# ProPrj_13cmPA-V1_V1_2025-12-29.net
KiCad netlist of a schematic drawn in EasyEDA Pro
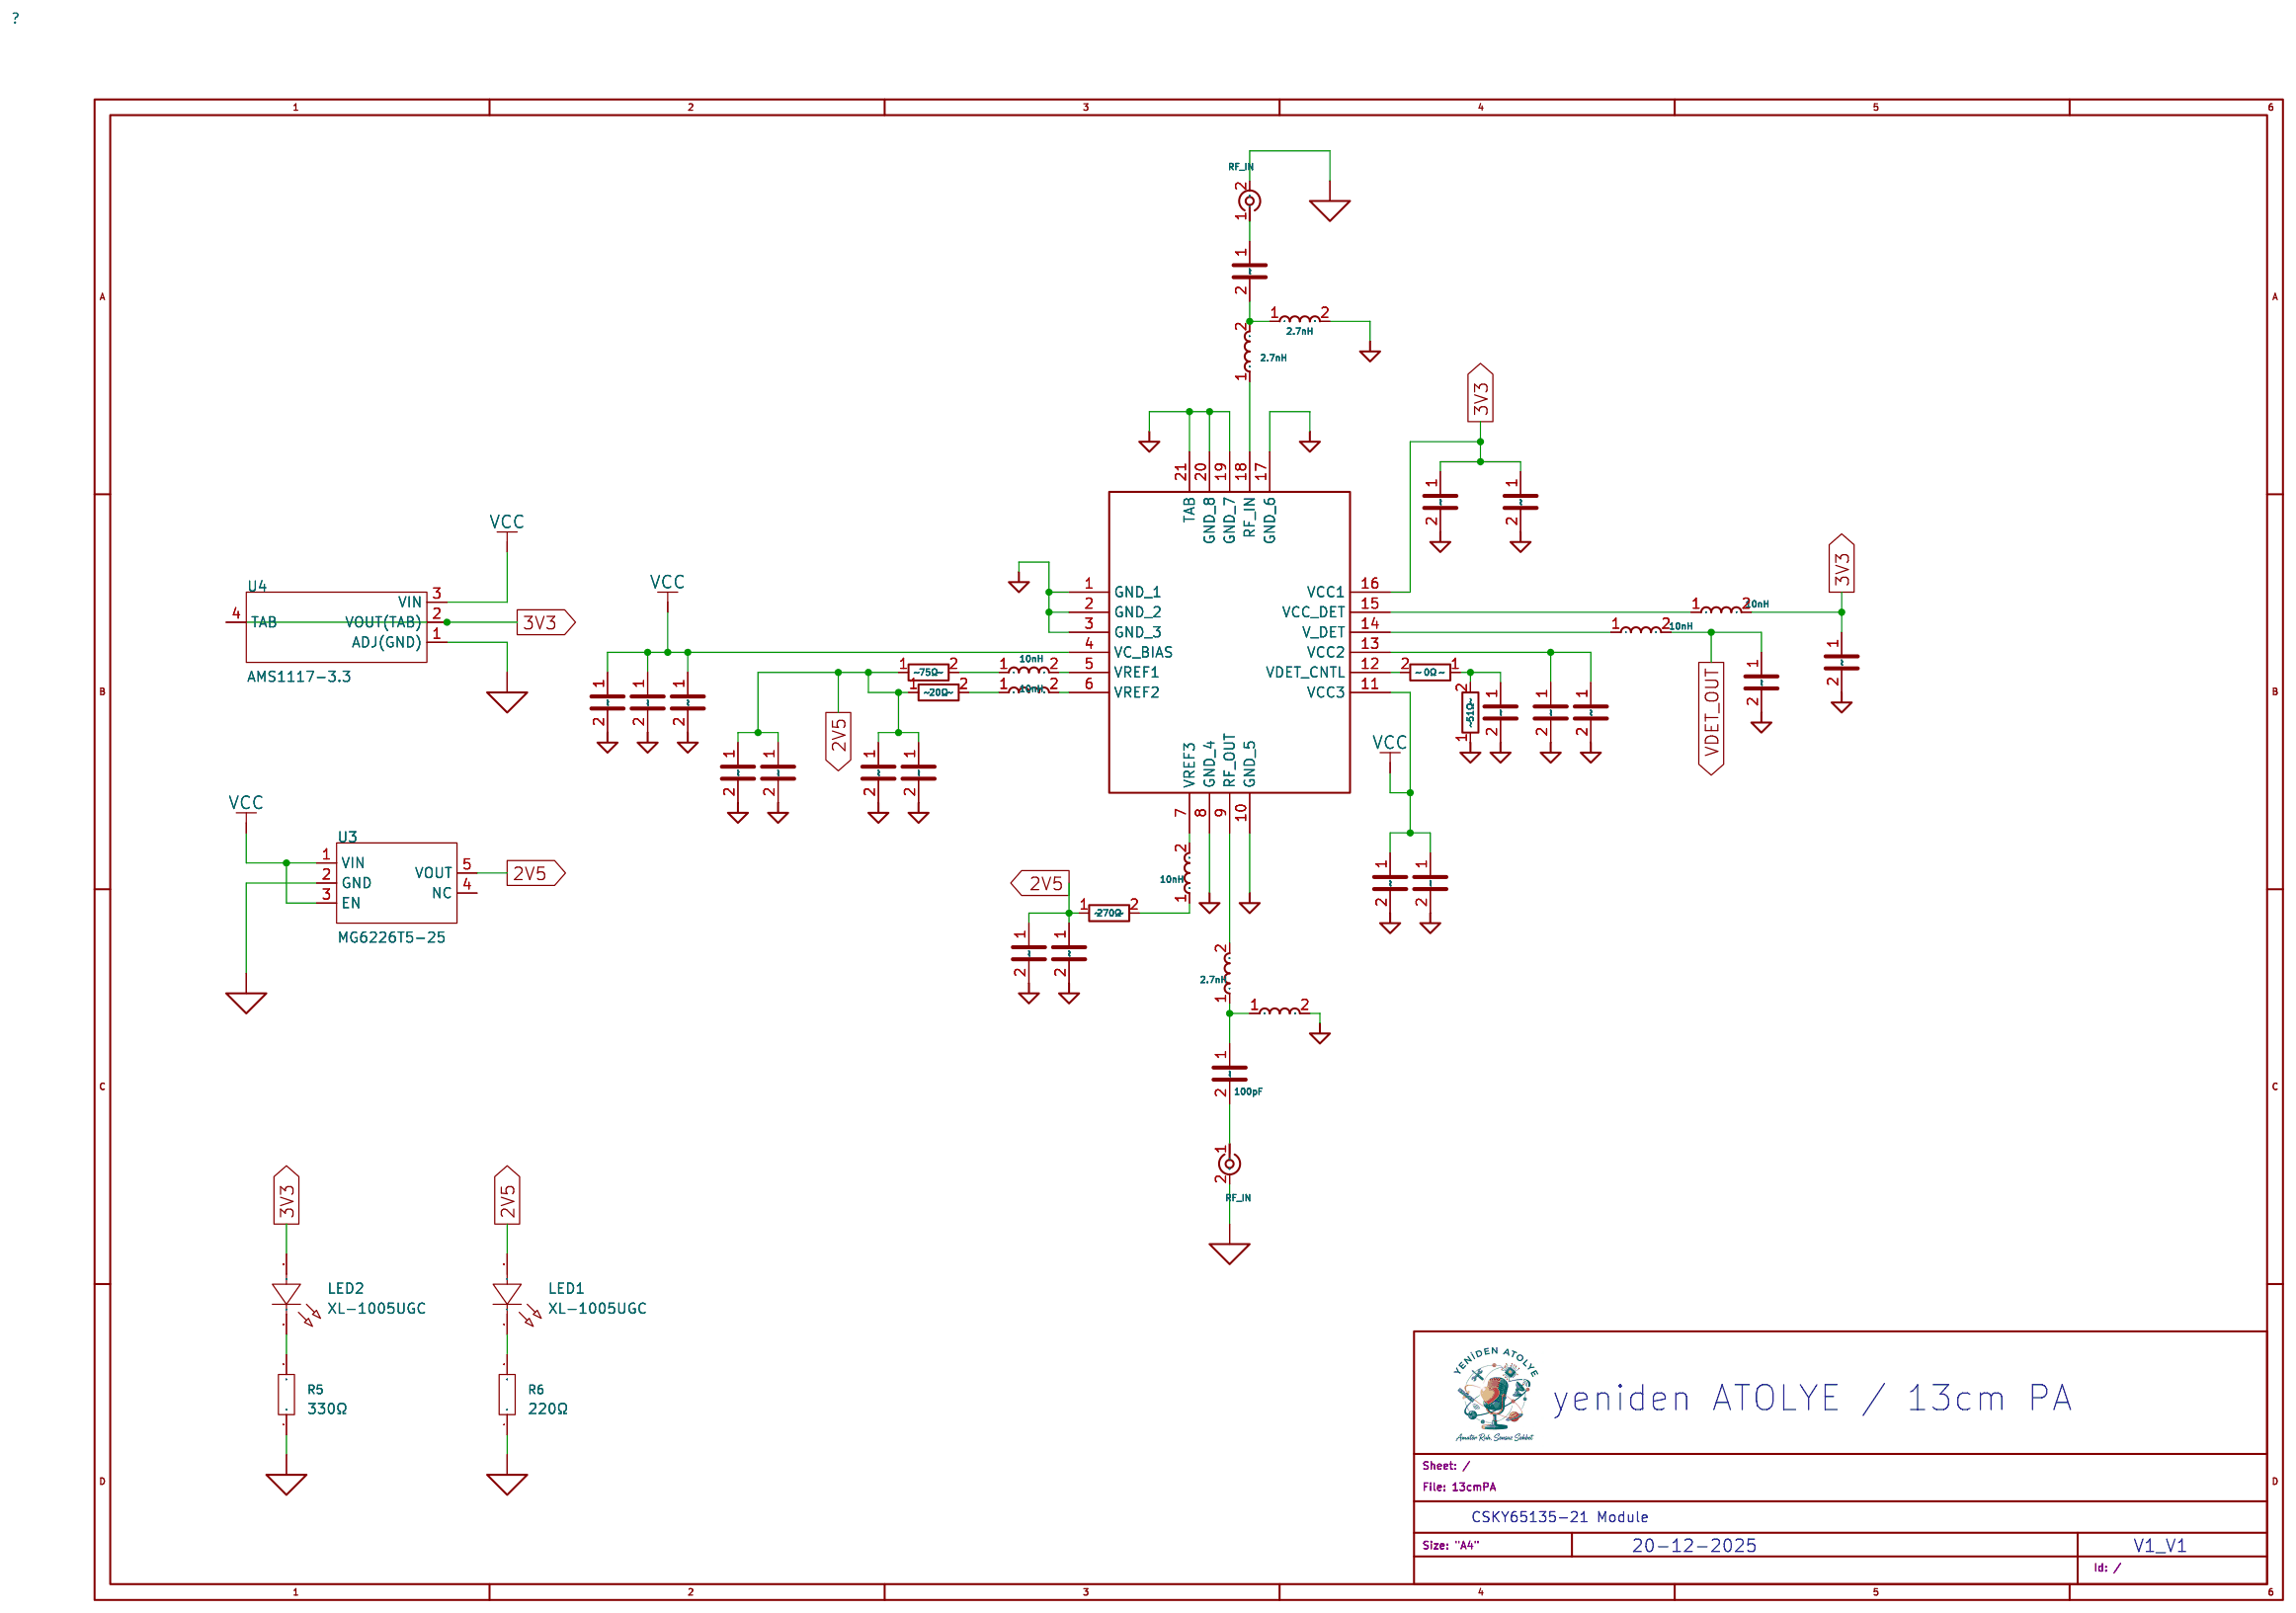
[diagram p0: schematic sheet]

(export (version "E")
  (design (tool "Eeschema 10.0.6"))
  (components
    (comp (ref "C1")
      (value "8.2pF")
      (footprint "easyedapro:Capacitor_SMD:C_0402_1005Metric")
      (description "Capacitance:8.2pF Voltage Rating:50V Temperature Coefficient:C0G")
      (fields (field (name "Manufacturer Part") "0402CG8R2C500NT") (field (name "Manufacturer") "FH(风华)"))
      (libsource (lib "easyedapro") (part "Device_C"))
    )
    (comp (ref "C2")
      (value "10uF")
      (footprint "easyedapro:Capacitor_SMD:C_0402_1005Metric")
      (description "Capacitance:10uF Tolerance:±10% Tolerance:±10% Voltage Rating:10V Temperature Coefficient:X7R")
      (fields (field (name "Manufacturer Part") "C0805X106K010T") (field (name "Manufacturer") "IHHEC(禾伸堂)"))
      (libsource (lib "easyedapro") (part "Device_C"))
    )
    (comp (ref "C3")
      (value "100nF")
      (footprint "easyedapro:Capacitor_SMD:C_0402_1005Metric")
      (description "Capacitance:100nF Tolerance:±10% Tolerance:±10% Voltage Rating:50V Temperature Coefficient:X7R")
      (fields (field (name "Manufacturer Part") "C0402X104K050T") (field (name "Manufacturer") "IHHEC(禾伸堂)"))
      (libsource (lib "easyedapro") (part "Device_C"))
    )
    (comp (ref "C4")
      (value "8.2pF")
      (footprint "easyedapro:Capacitor_SMD:C_0402_1005Metric")
      (description "Capacitance:8.2pF Voltage Rating:50V Temperature Coefficient:C0G")
      (fields (field (name "Manufacturer Part") "0402CG8R2C500NT") (field (name "Manufacturer") "FH(风华)"))
      (libsource (lib "easyedapro") (part "Device_C"))
    )
    (comp (ref "C5")
      (value "100nF")
      (footprint "easyedapro:Capacitor_SMD:C_0402_1005Metric")
      (description "Capacitance:100nF Tolerance:±10% Tolerance:±10% Voltage Rating:50V Temperature Coefficient:X7R")
      (fields (field (name "Manufacturer Part") "C0402X104K050T") (field (name "Manufacturer") "IHHEC(禾伸堂)"))
      (libsource (lib "easyedapro") (part "Device_C"))
    )
    (comp (ref "C6")
      (value "8.2pF")
      (footprint "easyedapro:Capacitor_SMD:C_0402_1005Metric")
      (description "Capacitance:8.2pF Voltage Rating:50V Temperature Coefficient:C0G")
      (fields (field (name "Manufacturer Part") "0402CG8R2C500NT") (field (name "Manufacturer") "FH(风华)"))
      (libsource (lib "easyedapro") (part "Device_C"))
    )
    (comp (ref "C7")
      (value "10uF")
      (footprint "easyedapro:Capacitor_SMD:C_0402_1005Metric")
      (description "Capacitance:10uF Tolerance:±10% Tolerance:±10% Voltage Rating:10V Temperature Coefficient:X7R")
      (fields (field (name "Manufacturer Part") "C0805X106K010T") (field (name "Manufacturer") "IHHEC(禾伸堂)"))
      (libsource (lib "easyedapro") (part "Device_C"))
    )
    (comp (ref "C8")
      (value "100nF")
      (footprint "easyedapro:Capacitor_SMD:C_0402_1005Metric")
      (description "Capacitance:100nF Tolerance:±10% Tolerance:±10% Voltage Rating:50V Temperature Coefficient:X7R")
      (fields (field (name "Manufacturer Part") "C0402X104K050T") (field (name "Manufacturer") "IHHEC(禾伸堂)"))
      (libsource (lib "easyedapro") (part "Device_C"))
    )
    (comp (ref "C9")
      (value "100nF")
      (footprint "easyedapro:Capacitor_SMD:C_0402_1005Metric")
      (description "Capacitance:100nF Tolerance:±10% Tolerance:±10% Voltage Rating:50V Temperature Coefficient:X7R")
      (fields (field (name "Manufacturer Part") "C0402X104K050T") (field (name "Manufacturer") "IHHEC(禾伸堂)"))
      (libsource (lib "easyedapro") (part "Device_C"))
    )
    (comp (ref "C10")
      (value "8.2pF")
      (footprint "easyedapro:Capacitor_SMD:C_0402_1005Metric")
      (description "Capacitance:8.2pF Voltage Rating:50V Temperature Coefficient:C0G")
      (fields (field (name "Manufacturer Part") "0402CG8R2C500NT") (field (name "Manufacturer") "FH(风华)"))
      (libsource (lib "easyedapro") (part "Device_C"))
    )
    (comp (ref "C11")
      (value "3.3nF")
      (footprint "easyedapro:Capacitor_SMD:C_0402_1005Metric")
      (description "Capacitance:3.3nF Tolerance:±10% Tolerance:±10% Voltage Rating:50V Temperature Coefficient:X7R")
      (fields
        (field (name "Manufacturer Part") "CC0402KRX7R9BB332")
        (field (name "Manufacturer") "YAGEO(国巨)")
      )
      (libsource (lib "easyedapro") (part "Device_C"))
    )
    (comp (ref "C12")
      (value "8.2pF")
      (footprint "easyedapro:Capacitor_SMD:C_0402_1005Metric")
      (description "Capacitance:8.2pF Voltage Rating:50V Temperature Coefficient:C0G")
      (fields (field (name "Manufacturer Part") "0402CG8R2C500NT") (field (name "Manufacturer") "FH(风华)"))
      (libsource (lib "easyedapro") (part "Device_C"))
    )
    (comp (ref "C13")
      (value "8.2pF")
      (footprint "easyedapro:Capacitor_SMD:C_0402_1005Metric")
      (description "Capacitance:8.2pF Voltage Rating:50V Temperature Coefficient:C0G")
      (fields (field (name "Manufacturer Part") "0402CG8R2C500NT") (field (name "Manufacturer") "FH(风华)"))
      (libsource (lib "easyedapro") (part "Device_C"))
    )
    (comp (ref "C14")
      (value "100nF")
      (footprint "easyedapro:Capacitor_SMD:C_0402_1005Metric")
      (description "Capacitance:100nF Tolerance:±10% Tolerance:±10% Voltage Rating:50V Temperature Coefficient:X7R")
      (fields (field (name "Manufacturer Part") "C0402X104K050T") (field (name "Manufacturer") "IHHEC(禾伸堂)"))
      (libsource (lib "easyedapro") (part "Device_C"))
    )
    (comp (ref "C15")
      (value "270pF")
      (footprint "easyedapro:Capacitor_SMD:C_0402_1005Metric")
      (description "Capacitance:270pF Tolerance:±10% Tolerance:±10% Voltage Rating:50V Temperature Coefficient:X7R")
      (fields
        (field (name "Manufacturer Part") "CC0402KRX7R9BB271")
        (field (name "Manufacturer") "YAGEO(国巨)")
      )
      (libsource (lib "easyedapro") (part "Device_C"))
    )
    (comp (ref "C16")
      (value "C0402A101J500NT")
      (footprint "easyedapro:Capacitor_SMD:C_0402_1005Metric")
      (fields (field (name "Manufacturer") "TORCH(火炬)"))
      (libsource (lib "easyedapro") (part "Device_C"))
    )
    (comp (ref "C17")
      (value "10uF")
      (footprint "easyedapro:Capacitor_SMD:C_0402_1005Metric")
      (description "Capacitance:10uF Tolerance:±10% Tolerance:±10% Voltage Rating:10V Temperature Coefficient:X7R")
      (fields (field (name "Manufacturer Part") "C0805X106K010T") (field (name "Manufacturer") "IHHEC(禾伸堂)"))
      (libsource (lib "easyedapro") (part "Device_C"))
    )
    (comp (ref "C18")
      (value "100pF")
      (footprint "easyedapro:Capacitor_SMD:C_0402_1005Metric")
      (description "Capacitance:100pF Tolerance:±5% Tolerance:±5% Voltage Rating:50V Temperature Coefficient:C0G")
      (fields
        (field (name "Manufacturer Part") "CL21C101JBANNNC")
        (field (name "Manufacturer") "SAMSUNG(三星)")
      )
      (libsource (lib "easyedapro") (part "Device_C"))
    )
    (comp (ref "C19")
      (value "100pF")
      (footprint "easyedapro:Capacitor_SMD:C_0402_1005Metric")
      (description "Capacitance:100pF Tolerance:±5% Tolerance:±5% Voltage Rating:50V Temperature Coefficient:C0G")
      (fields
        (field (name "Manufacturer Part") "CL21C101JBANNNC")
        (field (name "Manufacturer") "SAMSUNG(三星)")
      )
      (libsource (lib "easyedapro") (part "Device_C"))
    )
    (comp (ref "C20")
      (value "100nF")
      (footprint "easyedapro:Capacitor_SMD:C_0402_1005Metric")
      (description "Capacitance:100nF Tolerance:±10% Tolerance:±10% Voltage Rating:50V Temperature Coefficient:X7R")
      (fields (field (name "Manufacturer Part") "C0402X104K050T") (field (name "Manufacturer") "IHHEC(禾伸堂)"))
      (libsource (lib "easyedapro") (part "Device_C"))
    )
    (comp (ref "IC1")
      (value "SKY65135-21")
      (footprint "easyedapro:QFN100P600X600X155-21N")
      (libsource (lib "easyedapro") (part "SKY65135-21_SKY65135-21"))
    )
    (comp (ref "J1")
      (value "RF_IN")
      (footprint "easyedapro:Connector_Coaxial:SMA_Amphenol_132289_EdgeMount")
      (description "small coaxial connector (BNC, SMA, SMB, SMC, Cinch/RCA, LEMO, ...)")
      (libsource (lib "easyedapro") (part "Connector_Conn_Coaxial_Small"))
    )
    (comp (ref "J2")
      (value "RF_IN")
      (footprint "easyedapro:Connector_Coaxial:SMA_Amphenol_132289_EdgeMount")
      (description "small coaxial connector (BNC, SMA, SMB, SMC, Cinch/RCA, LEMO, ...)")
      (libsource (lib "easyedapro") (part "Connector_Conn_Coaxial_Small"))
    )
    (comp (ref "L1")
      (value "10nH")
      (footprint "easyedapro:Inductor_SMD:L_0402_1005Metric")
      (fields (field (name "Manufacturer Part") "LQG15HS10NJ02D") (field (name "Manufacturer") "muRata(村田)"))
      (libsource (lib "easyedapro") (part "Device_L"))
    )
    (comp (ref "L2")
      (value "10nH")
      (footprint "easyedapro:Inductor_SMD:L_0402_1005Metric")
      (fields (field (name "Manufacturer Part") "LQG15HS10NJ02D") (field (name "Manufacturer") "muRata(村田)"))
      (libsource (lib "easyedapro") (part "Device_L"))
    )
    (comp (ref "L3")
      (value "2.7nH")
      (footprint "easyedapro:Inductor_SMD:L_0402_1005Metric")
      (fields (field (name "Manufacturer Part") "MLG1005S2N7BT000") (field (name "Manufacturer") "TDK"))
      (libsource (lib "easyedapro") (part "Device_L"))
    )
    (comp (ref "L4")
      (value "2.7nH")
      (footprint "easyedapro:Inductor_SMD:L_0402_1005Metric")
      (fields (field (name "Manufacturer Part") "MLG1005S2N7BT000") (field (name "Manufacturer") "TDK"))
      (libsource (lib "easyedapro") (part "Device_L"))
    )
    (comp (ref "L5")
      (value "2.7nH")
      (footprint "easyedapro:Inductor_SMD:L_0402_1005Metric")
      (fields (field (name "Manufacturer Part") "MLG1005S2N7BT000") (field (name "Manufacturer") "TDK"))
      (libsource (lib "easyedapro") (part "Device_L"))
    )
    (comp (ref "L6")
      (value "2.7nH")
      (footprint "easyedapro:Inductor_SMD:L_0402_1005Metric")
      (fields (field (name "Manufacturer Part") "MLG1005S2N7BT000") (field (name "Manufacturer") "TDK"))
      (libsource (lib "easyedapro") (part "Device_L"))
    )
    (comp (ref "L7")
      (value "10nH")
      (footprint "easyedapro:Inductor_SMD:L_0402_1005Metric")
      (fields (field (name "Manufacturer Part") "LQG15HS10NJ02D") (field (name "Manufacturer") "muRata(村田)"))
      (libsource (lib "easyedapro") (part "Device_L"))
    )
    (comp (ref "L8")
      (value "10nH")
      (footprint "easyedapro:Inductor_SMD:L_0402_1005Metric")
      (fields (field (name "Manufacturer Part") "LQG15HS10NJ02D") (field (name "Manufacturer") "muRata(村田)"))
      (libsource (lib "easyedapro") (part "Device_L"))
    )
    (comp (ref "L9")
      (value "10nH")
      (footprint "easyedapro:Inductor_SMD:L_0402_1005Metric")
      (fields (field (name "Manufacturer Part") "LQG15HS10NJ02D") (field (name "Manufacturer") "muRata(村田)"))
      (libsource (lib "easyedapro") (part "Device_L"))
    )
    (comp (ref "LED1")
      (value "XL-1005UGC")
      (footprint "easyedapro:LED0402-RD_GREEN")
      (fields (field (name "Manufacturer") "XINGLIGHT(成兴光)"))
      (libsource (lib "easyedapro") (part "XL-1005UGC"))
    )
    (comp (ref "LED2")
      (value "XL-1005UGC")
      (footprint "easyedapro:LED0402-RD_GREEN")
      (fields (field (name "Manufacturer") "XINGLIGHT(成兴光)"))
      (libsource (lib "easyedapro") (part "XL-1005UGC"))
    )
    (comp (ref "R1")
      (value "75Ω")
      (footprint "easyedapro:Resistor_SMD:R_0402_1005Metric")
      (fields (field (name "Manufacturer Part") "CR0402FF75R0G") (field (name "Manufacturer") "LIZ(丽智电子)"))
      (libsource (lib "easyedapro") (part "Device_R"))
    )
    (comp (ref "R2")
      (value "20Ω")
      (footprint "easyedapro:Resistor_SMD:R_0402_1005Metric")
      (fields (field (name "Manufacturer Part") "CR0402FF20R0G") (field (name "Manufacturer") "LIZ(丽智电子)"))
      (libsource (lib "easyedapro") (part "Device_R"))
    )
    (comp (ref "R3")
      (value "0Ω")
      (footprint "easyedapro:Resistor_SMD:R_0402_1005Metric")
      (fields (field (name "Manufacturer Part") "SCR0402J0R") (field (name "Manufacturer") "VO(翔胜)"))
      (libsource (lib "easyedapro") (part "Device_R"))
    )
    (comp (ref "R4")
      (value "51Ω")
      (footprint "easyedapro:Resistor_SMD:R_0402_1005Metric")
      (fields (field (name "Manufacturer Part") "RC0402FR-0751RL") (field (name "Manufacturer") "YAGEO(国巨)"))
      (libsource (lib "easyedapro") (part "Device_R"))
    )
    (comp (ref "R5")
      (value "330Ω")
      (footprint "easyedapro:R0402")
      (fields
        (field (name "Manufacturer Part") "0402WGF3300TCE")
        (field (name "Manufacturer") "UNI-ROYAL(厚声)")
      )
      (libsource (lib "easyedapro") (part "0402WGF3300TCE"))
    )
    (comp (ref "R6")
      (value "220Ω")
      (footprint "easyedapro:R0402")
      (fields
        (field (name "Manufacturer Part") "0402WGF2200TCE")
        (field (name "Manufacturer") "UNI-ROYAL(厚声)")
      )
      (libsource (lib "easyedapro") (part "0402WGF2200TCE"))
    )
    (comp (ref "R7")
      (value "270Ω")
      (footprint "easyedapro:Resistor_SMD:R_0402_1005Metric")
      (fields (field (name "Manufacturer Part") "CR0402JF0271G") (field (name "Manufacturer") "LIZ(丽智电子)"))
      (libsource (lib "easyedapro") (part "Device_R"))
    )
    (comp (ref "U3")
      (value "MG6226T5-25")
      (footprint "easyedapro:SOT-23-5_L2.9-W1.6-P0.95-LS2.8-BL")
      (fields (field (name "Manufacturer") "Megain(美佳音)"))
      (libsource (lib "easyedapro") (part "MG6226T5-25"))
    )
    (comp (ref "U4")
      (value "AMS1117-3.3")
      (footprint "easyedapro:SOT-223-4_L6.5-W3.5-P2.30-LS7.0-BR")
      (fields (field (name "Manufacturer") "UMW(友台半导体)"))
      (libsource (lib "easyedapro") (part "AMS1117-3.3_C347222"))
    )
  )
  (nets
    (net (code "1") (name "2V5") (class "Default")
      (node (ref "C10") (pin "1") (pinfunction "~_1") (pintype "unspecified"))
      (node (ref "C3") (pin "1") (pinfunction "~_1") (pintype "unspecified"))
      (node (ref "C4") (pin "1") (pinfunction "~_1") (pintype "unspecified"))
      (node (ref "C5") (pin "1") (pinfunction "~_1") (pintype "unspecified"))
      (node (ref "C6") (pin "1") (pinfunction "~_1") (pintype "unspecified"))
      (node (ref "C9") (pin "1") (pinfunction "~_1") (pintype "unspecified"))
      (node (ref "LED1") (pin "2") (pinfunction "A_2") (pintype "unspecified"))
      (node (ref "R1") (pin "1") (pinfunction "~_1") (pintype "unspecified"))
      (node (ref "R2") (pin "1") (pinfunction "~_1") (pintype "unspecified"))
      (node (ref "R7") (pin "1") (pinfunction "~_1") (pintype "unspecified"))
      (node (ref "U3") (pin "5") (pinfunction "VOUT_5") (pintype "unspecified"))
    )
    (net (code "2") (name "3V3") (class "Default")
      (node (ref "C11") (pin "1") (pinfunction "~_1") (pintype "unspecified"))
      (node (ref "C7") (pin "1") (pinfunction "~_1") (pintype "unspecified"))
      (node (ref "C8") (pin "1") (pinfunction "~_1") (pintype "unspecified"))
      (node (ref "IC1") (pin "16") (pinfunction "VCC1_16") (pintype "unspecified"))
      (node (ref "L1") (pin "2") (pinfunction "2_2") (pintype "unspecified"))
      (node (ref "LED2") (pin "2") (pinfunction "A_2") (pintype "unspecified"))
      (node (ref "U4") (pin "2") (pinfunction "VOUT(TAB)_2") (pintype "unspecified"))
      (node (ref "U4") (pin "4") (pinfunction "TAB_4") (pintype "unspecified"))
    )
    (net (code "3") (name "GND") (class "Default")
      (node (ref "C1") (pin "2") (pinfunction "~_2") (pintype "unspecified"))
      (node (ref "C10") (pin "2") (pinfunction "~_2") (pintype "unspecified"))
      (node (ref "C11") (pin "2") (pinfunction "~_2") (pintype "unspecified"))
      (node (ref "C12") (pin "2") (pinfunction "~_2") (pintype "unspecified"))
      (node (ref "C13") (pin "2") (pinfunction "~_2") (pintype "unspecified"))
      (node (ref "C14") (pin "2") (pinfunction "~_2") (pintype "unspecified"))
      (node (ref "C15") (pin "2") (pinfunction "~_2") (pintype "unspecified"))
      (node (ref "C16") (pin "2") (pinfunction "~_2") (pintype "unspecified"))
      (node (ref "C17") (pin "2") (pinfunction "~_2") (pintype "unspecified"))
      (node (ref "C2") (pin "2") (pinfunction "~_2") (pintype "unspecified"))
      (node (ref "C20") (pin "2") (pinfunction "~_2") (pintype "unspecified"))
      (node (ref "C3") (pin "2") (pinfunction "~_2") (pintype "unspecified"))
      (node (ref "C4") (pin "2") (pinfunction "~_2") (pintype "unspecified"))
      (node (ref "C5") (pin "2") (pinfunction "~_2") (pintype "unspecified"))
      (node (ref "C6") (pin "2") (pinfunction "~_2") (pintype "unspecified"))
      (node (ref "C7") (pin "2") (pinfunction "~_2") (pintype "unspecified"))
      (node (ref "C8") (pin "2") (pinfunction "~_2") (pintype "unspecified"))
      (node (ref "C9") (pin "2") (pinfunction "~_2") (pintype "unspecified"))
      (node (ref "IC1") (pin "1") (pinfunction "GND_1_1") (pintype "unspecified"))
      (node (ref "IC1") (pin "10") (pinfunction "GND_5_10") (pintype "unspecified"))
      (node (ref "IC1") (pin "17") (pinfunction "GND_6_17") (pintype "unspecified"))
      (node (ref "IC1") (pin "19") (pinfunction "GND_7_19") (pintype "unspecified"))
      (node (ref "IC1") (pin "2") (pinfunction "GND_2_2") (pintype "unspecified"))
      (node (ref "IC1") (pin "20") (pinfunction "GND_8_20") (pintype "unspecified"))
      (node (ref "IC1") (pin "21") (pinfunction "TAB_21") (pintype "unspecified"))
      (node (ref "IC1") (pin "3") (pinfunction "GND_3_3") (pintype "unspecified"))
      (node (ref "IC1") (pin "8") (pinfunction "GND_4_8") (pintype "unspecified"))
      (node (ref "J1") (pin "2") (pinfunction "Ext_2") (pintype "unspecified"))
      (node (ref "J2") (pin "2") (pinfunction "Ext_2") (pintype "unspecified"))
      (node (ref "L4") (pin "2") (pinfunction "2_2") (pintype "unspecified"))
      (node (ref "L6") (pin "2") (pinfunction "2_2") (pintype "unspecified"))
      (node (ref "R4") (pin "1") (pinfunction "~_1") (pintype "unspecified"))
      (node (ref "R5") (pin "1") (pinfunction "1_1") (pintype "input"))
      (node (ref "R6") (pin "1") (pinfunction "1_1") (pintype "input"))
      (node (ref "U3") (pin "2") (pinfunction "GND_2") (pintype "unspecified"))
      (node (ref "U4") (pin "1") (pinfunction "ADJ(GND)_1") (pintype "unspecified"))
    )
    (net (code "4") (name "Net-(C15-~-Pad1)") (class "Default")
      (node (ref "C15") (pin "1") (pinfunction "~_1") (pintype "unspecified"))
      (node (ref "R3") (pin "1") (pinfunction "~_1") (pintype "unspecified"))
      (node (ref "R4") (pin "2") (pinfunction "~_2") (pintype "unspecified"))
    )
    (net (code "5") (name "Net-(C18-~-Pad2)") (class "Default")
      (node (ref "C18") (pin "2") (pinfunction "~_2") (pintype "unspecified"))
      (node (ref "L3") (pin "2") (pinfunction "2_2") (pintype "unspecified"))
      (node (ref "L4") (pin "1") (pinfunction "1_1") (pintype "unspecified"))
    )
    (net (code "6") (name "Net-(C19-~-Pad1)") (class "Default")
      (node (ref "C19") (pin "1") (pinfunction "~_1") (pintype "unspecified"))
      (node (ref "L5") (pin "1") (pinfunction "1_1") (pintype "unspecified"))
      (node (ref "L6") (pin "1") (pinfunction "1_1") (pintype "unspecified"))
    )
    (net (code "7") (name "Net-(IC1-RF_IN)") (class "Default")
      (node (ref "IC1") (pin "18") (pinfunction "RF_IN_18") (pintype "input"))
      (node (ref "L3") (pin "1") (pinfunction "1_1") (pintype "unspecified"))
    )
    (net (code "8") (name "Net-(IC1-RF_OUT)") (class "Default")
      (node (ref "IC1") (pin "9") (pinfunction "RF_OUT_9") (pintype "output"))
      (node (ref "L5") (pin "2") (pinfunction "2_2") (pintype "unspecified"))
    )
    (net (code "9") (name "Net-(IC1-VCC2)") (class "Default")
      (node (ref "C13") (pin "1") (pinfunction "~_1") (pintype "unspecified"))
      (node (ref "C14") (pin "1") (pinfunction "~_1") (pintype "unspecified"))
      (node (ref "IC1") (pin "13") (pinfunction "VCC2_13") (pintype "unspecified"))
    )
    (net (code "10") (name "Net-(IC1-VCC_DET)") (class "Default")
      (node (ref "IC1") (pin "15") (pinfunction "VCC_DET_15") (pintype "unspecified"))
      (node (ref "L1") (pin "1") (pinfunction "1_1") (pintype "unspecified"))
    )
    (net (code "11") (name "Net-(IC1-VDET_CNTL)") (class "Default")
      (node (ref "IC1") (pin "12") (pinfunction "VDET_CNTL_12") (pintype "unspecified"))
      (node (ref "R3") (pin "2") (pinfunction "~_2") (pintype "unspecified"))
    )
    (net (code "12") (name "Net-(IC1-VREF1)") (class "Default")
      (node (ref "IC1") (pin "5") (pinfunction "VREF1_5") (pintype "input"))
      (node (ref "L8") (pin "2") (pinfunction "2_2") (pintype "unspecified"))
    )
    (net (code "13") (name "Net-(IC1-VREF2)") (class "Default")
      (node (ref "IC1") (pin "6") (pinfunction "VREF2_6") (pintype "input"))
      (node (ref "L9") (pin "2") (pinfunction "2_2") (pintype "unspecified"))
    )
    (net (code "14") (name "Net-(IC1-VREF3)") (class "Default")
      (node (ref "IC1") (pin "7") (pinfunction "VREF3_7") (pintype "input"))
      (node (ref "L7") (pin "2") (pinfunction "2_2") (pintype "unspecified"))
    )
    (net (code "15") (name "Net-(IC1-V_DET)") (class "Default")
      (node (ref "IC1") (pin "14") (pinfunction "V_DET_14") (pintype "unspecified"))
      (node (ref "L2") (pin "1") (pinfunction "1_1") (pintype "unspecified"))
    )
    (net (code "16") (name "Net-(J1-In)") (class "Default")
      (node (ref "C18") (pin "1") (pinfunction "~_1") (pintype "unspecified"))
      (node (ref "J1") (pin "1") (pinfunction "In_1") (pintype "unspecified"))
    )
    (net (code "17") (name "Net-(J2-In)") (class "Default")
      (node (ref "C19") (pin "2") (pinfunction "~_2") (pintype "unspecified"))
      (node (ref "J2") (pin "1") (pinfunction "In_1") (pintype "unspecified"))
    )
    (net (code "18") (name "Net-(L7-Pad1)") (class "Default")
      (node (ref "L7") (pin "1") (pinfunction "1_1") (pintype "unspecified"))
      (node (ref "R7") (pin "2") (pinfunction "~_2") (pintype "unspecified"))
    )
    (net (code "19") (name "Net-(L8-Pad1)") (class "Default")
      (node (ref "L8") (pin "1") (pinfunction "1_1") (pintype "unspecified"))
      (node (ref "R1") (pin "2") (pinfunction "~_2") (pintype "unspecified"))
    )
    (net (code "20") (name "Net-(L9-Pad1)") (class "Default")
      (node (ref "L9") (pin "1") (pinfunction "1_1") (pintype "unspecified"))
      (node (ref "R2") (pin "2") (pinfunction "~_2") (pintype "unspecified"))
    )
    (net (code "21") (name "Net-(LED1-K)") (class "Default")
      (node (ref "LED1") (pin "1") (pinfunction "K_1") (pintype "unspecified"))
      (node (ref "R6") (pin "2") (pinfunction "2_2") (pintype "input"))
    )
    (net (code "22") (name "Net-(LED2-K)") (class "Default")
      (node (ref "LED2") (pin "1") (pinfunction "K_1") (pintype "unspecified"))
      (node (ref "R5") (pin "2") (pinfunction "2_2") (pintype "input"))
    )
    (net (code "23") (name "VCC") (class "Default")
      (node (ref "C1") (pin "1") (pinfunction "~_1") (pintype "unspecified"))
      (node (ref "C16") (pin "1") (pinfunction "~_1") (pintype "unspecified"))
      (node (ref "C17") (pin "1") (pinfunction "~_1") (pintype "unspecified"))
      (node (ref "C2") (pin "1") (pinfunction "~_1") (pintype "unspecified"))
      (node (ref "C20") (pin "1") (pinfunction "~_1") (pintype "unspecified"))
      (node (ref "IC1") (pin "11") (pinfunction "VCC3_11") (pintype "unspecified"))
      (node (ref "IC1") (pin "4") (pinfunction "VC_BIAS_4") (pintype "unspecified"))
      (node (ref "U3") (pin "1") (pinfunction "VIN_1") (pintype "unspecified"))
      (node (ref "U3") (pin "3") (pinfunction "EN_3") (pintype "unspecified"))
      (node (ref "U4") (pin "3") (pinfunction "VIN_3") (pintype "unspecified"))
    )
    (net (code "24") (name "VDET_OUT") (class "Default")
      (node (ref "C12") (pin "1") (pinfunction "~_1") (pintype "unspecified"))
      (node (ref "L2") (pin "2") (pinfunction "2_2") (pintype "unspecified"))
    )
    (net (code "25") (name "unconnected-(U3-NC-Pad4)") (class "Default")
      (node (ref "U3") (pin "4") (pinfunction "NC_4") (pintype "unspecified"))
    )
  )
)
